# audio-amplifier-PAM8302A.net
KiCad netlist of a schematic drawn in EAGLE
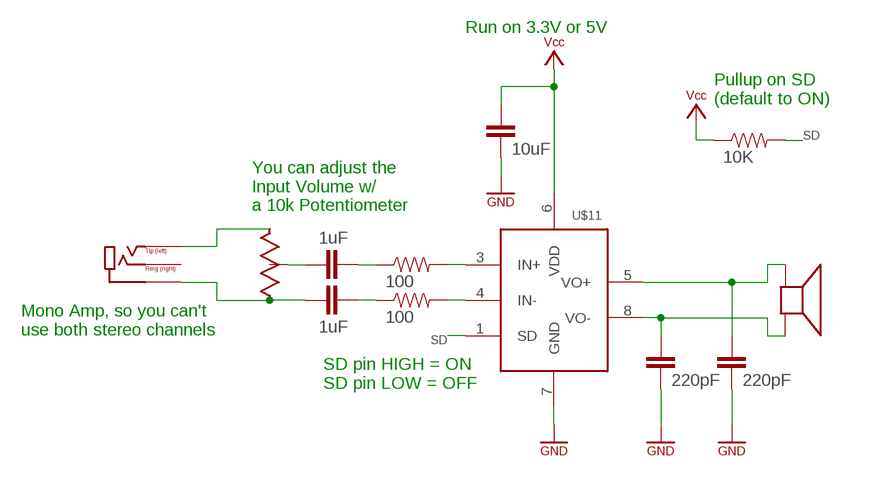
[diagram p0: schematic, sheet 1]

(export (version "E")
  (design (tool "Eeschema 10.0.6"))
  (components
    (comp (ref "C1")
      (value "1uF")
      (footprint "eagle-import:0805")
      (libsource (lib "eagle-import") (part "COMPONENT_CAP-0805"))
    )
    (comp (ref "C2")
      (value "1uF")
      (footprint "eagle-import:0805")
      (libsource (lib "eagle-import") (part "COMPONENT_CAP-0805"))
    )
    (comp (ref "C3")
      (value "10uF")
      (footprint "eagle-import:0805")
      (libsource (lib "eagle-import") (part "COMPONENT_CAP-0805"))
    )
    (comp (ref "C4")
      (value "220pF")
      (footprint "eagle-import:0805")
      (libsource (lib "eagle-import") (part "COMPONENT_CAP-0805"))
    )
    (comp (ref "C5")
      (value "220pF")
      (footprint "eagle-import:0805")
      (libsource (lib "eagle-import") (part "COMPONENT_CAP-0805"))
    )
    (comp (ref "R1")
      (value "100")
      (footprint "eagle-import:0805")
      (libsource (lib "eagle-import") (part "COMPONENT_RESISTOR-0805"))
    )
    (comp (ref "R2")
      (value "100")
      (footprint "eagle-import:0805")
      (libsource (lib "eagle-import") (part "COMPONENT_RESISTOR-0805"))
    )
    (comp (ref "R3")
      (value "10K")
      (footprint "eagle-import:0805")
      (libsource (lib "eagle-import") (part "COMPONENT_RESISTOR-0805"))
    )
    (comp (ref "SP1")
      (value "MISC_SPEAKER/PS12")
      (footprint "eagle-import:SPEAKER_PS12")
      (libsource (lib "eagle-import") (part "MISC_SPEAKER/PS12"))
    )
    (comp (ref "U$1")
      (value "CONN_AUDIO_HEADPHONE")
      (footprint "eagle-import:SJ2-35853A-SMT-TR")
      (libsource (lib "eagle-import") (part "CONN_AUDIO_HEADPHONE"))
    )
    (comp (ref "U$10")
      (value "10k")
      (footprint "eagle-import:TC33X-2-103E")
      (libsource (lib "eagle-import") (part "COMPONENT_POTENTIOMETER"))
    )
    (comp (ref "U$11")
      (value "IC_AUDIO_AMP_PAM8302A")
      (footprint "eagle-import:SOIC8")
      (libsource (lib "eagle-import") (part "IC_AUDIO_AMP_PAM8302A"))
    )
  )
  (nets
    (net (code "1") (name "Net-(C1-Pad2)") (class "Default")
      (node (ref "C1") (pin "2") (pinfunction "2_2") (pintype "passive"))
      (node (ref "R1") (pin "1") (pinfunction "1_1") (pintype "passive"))
    )
    (net (code "2") (name "Net-(C2-Pad2)") (class "Default")
      (node (ref "C2") (pin "2") (pinfunction "2_2") (pintype "passive"))
      (node (ref "R2") (pin "1") (pinfunction "1_1") (pintype "passive"))
    )
    (net (code "3") (name "Net-(SP1-+)") (class "Default")
      (node (ref "C5") (pin "1") (pinfunction "1_1") (pintype "passive"))
      (node (ref "SP1") (pin "P$1") (pinfunction "+_P$1") (pintype "passive"))
      (node (ref "U$11") (pin "5") (pinfunction "VO+_5") (pintype "bidirectional"))
    )
    (net (code "4") (name "Net-(SP1--)") (class "Default")
      (node (ref "C4") (pin "1") (pinfunction "1_1") (pintype "passive"))
      (node (ref "SP1") (pin "P$2") (pinfunction "-_P$2") (pintype "passive"))
      (node (ref "U$11") (pin "8") (pinfunction "VO-_8") (pintype "bidirectional"))
    )
    (net (code "5") (name "Net-(U$1-SLEEVE)") (class "Default")
      (node (ref "C2") (pin "1") (pinfunction "1_1") (pintype "passive"))
      (node (ref "U$1") (pin "1") (pinfunction "SLEEVE_1") (pintype "bidirectional"))
      (node (ref "U$10") (pin "3") (pinfunction "B_3") (pintype "bidirectional"))
    )
    (net (code "6") (name "Net-(U$1-TIP)") (class "Default")
      (node (ref "U$1") (pin "2") (pinfunction "TIP_2") (pintype "bidirectional"))
      (node (ref "U$10") (pin "1") (pinfunction "A_1") (pintype "bidirectional"))
    )
    (net (code "7") (name "Net-(U$10-WIPER)") (class "Default")
      (node (ref "C1") (pin "1") (pinfunction "1_1") (pintype "passive"))
      (node (ref "U$10") (pin "2") (pinfunction "WIPER_2") (pintype "bidirectional"))
    )
    (net (code "8") (name "Net-(U$11-IN+)") (class "Default")
      (node (ref "R1") (pin "2") (pinfunction "2_2") (pintype "passive"))
      (node (ref "U$11") (pin "3") (pinfunction "IN+_3") (pintype "bidirectional"))
    )
    (net (code "9") (name "Net-(U$11-IN-)") (class "Default")
      (node (ref "R2") (pin "2") (pinfunction "2_2") (pintype "passive"))
      (node (ref "U$11") (pin "4") (pinfunction "IN-_4") (pintype "bidirectional"))
    )
    (net (code "10") (name "SD") (class "Default")
      (node (ref "R3") (pin "2") (pinfunction "2_2") (pintype "passive"))
      (node (ref "U$11") (pin "1") (pinfunction "SD_1") (pintype "bidirectional"))
    )
    (net (code "11") (name "SYMBOL_GND") (class "Default")
      (node (ref "C3") (pin "2") (pinfunction "2_2") (pintype "passive"))
      (node (ref "C4") (pin "2") (pinfunction "2_2") (pintype "passive"))
      (node (ref "C5") (pin "2") (pinfunction "2_2") (pintype "passive"))
      (node (ref "U$11") (pin "7") (pinfunction "GND_7") (pintype "bidirectional"))
    )
    (net (code "12") (name "SYMBOL_VCC") (class "Default")
      (node (ref "C3") (pin "1") (pinfunction "1_1") (pintype "passive"))
      (node (ref "R3") (pin "1") (pinfunction "1_1") (pintype "passive"))
      (node (ref "U$11") (pin "6") (pinfunction "VDD_6") (pintype "bidirectional"))
    )
    (net (code "13") (name "unconnected-(U$1-RING-Pad3)") (class "Default")
      (node (ref "U$1") (pin "3") (pinfunction "RING_3") (pintype "bidirectional"))
    )
  )
)
